# Sensor_Board.net
KiCad netlist of a schematic drawn in Altium Designer
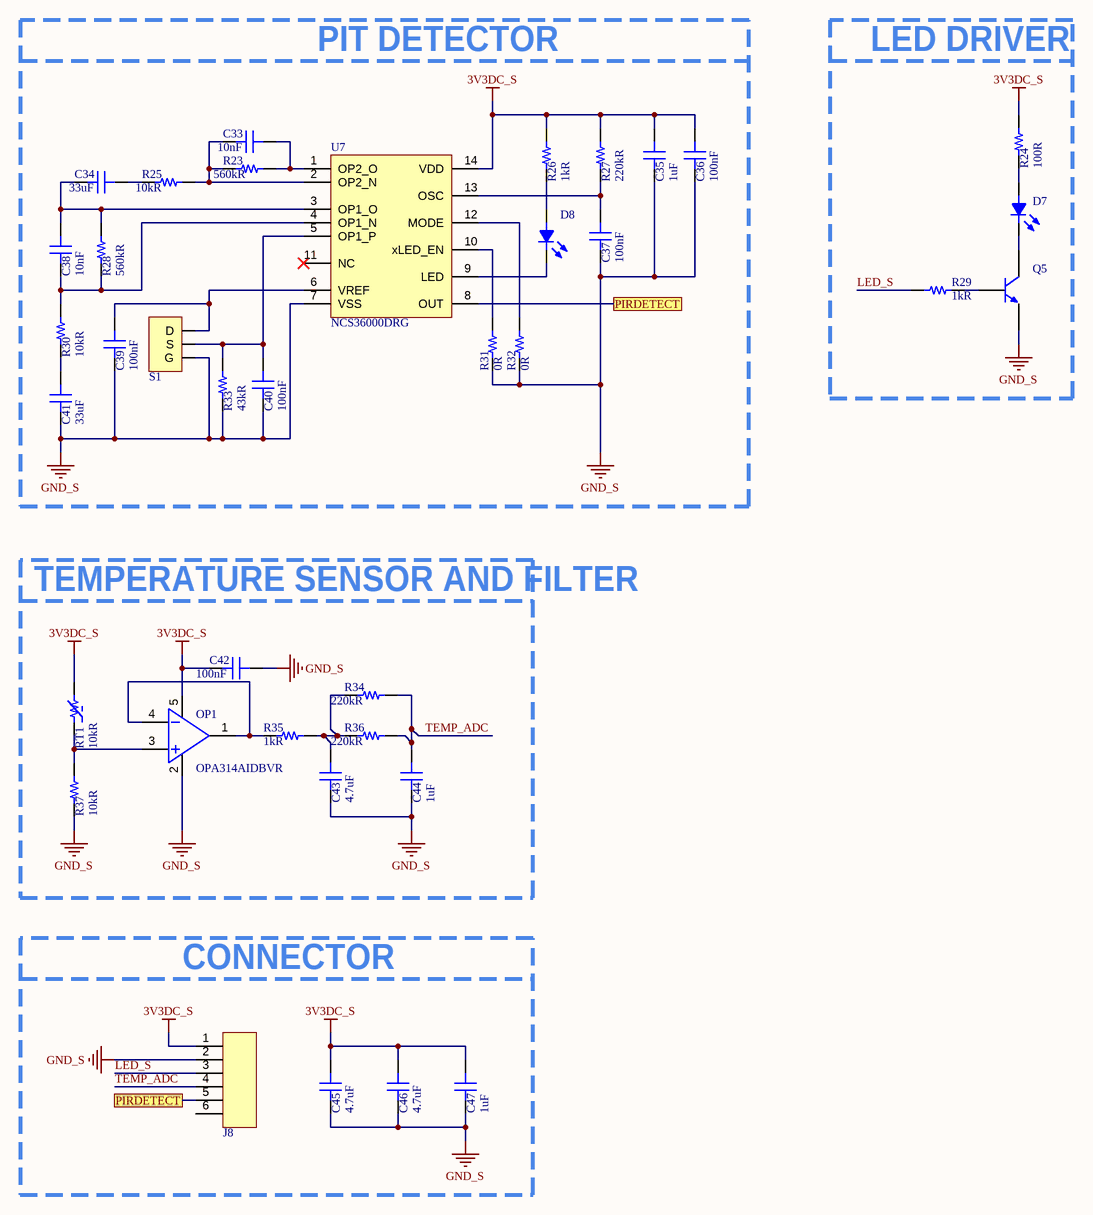
[diagram p0: Sensor_Board.SchDoc]

(export (version "E")
  (design (tool "Eeschema 10.0.6"))
  (components
    (comp (ref "C33")
      (value "0603B103K160CT")
      (footprint "C0603_CER")
      (description "CAP CER 10nF %10 0603 SMD")
      (fields
        (field (name "MANUFACTURER") "Walsin Technologies")
        (field (name "TOLERANCE") "10%")
        (field (name "CAPACITANCE") "10nF")
        (field (name "DESIGNED BY") "Süleyman ARIKAYA")
      )
      (libsource (lib "Arikaya_Lib") (part "CAP CER 10nF 0603"))
    )
    (comp (ref "C34")
      (value "C3216X5R1E336M160AC")
      (footprint "C1206_CER")
      (description "CAP CER 33uF %20 25V 1206 SMD")
      (fields
        (field (name "MANUFACTURER") "TDK")
        (field (name "TOLERANCE") "20%")
        (field (name "CAPACITANCE") "33uF")
        (field (name "DESIGNED BY") "Süleyman ARIKAYA")
      )
      (libsource (lib "Arikaya_Lib") (part "CAP CER 33uF 1206"))
    )
    (comp (ref "C35")
      (value "CL21B105KBFNNNE")
      (footprint "C0805_CER")
      (description "CAP CER 1uF %10 50V X7R 0805 SMD")
      (fields
        (field (name "MANUFACTURER") "Samsung")
        (field (name "TOLERANCE") "10%")
        (field (name "CAPACITANCE") "1uF")
        (field (name "DESIGNED BY") "Süleyman ARIKAYA")
      )
      (libsource (lib "Arikaya_Lib") (part "CAP CER 1uF 0805"))
    )
    (comp (ref "C36")
      (value "C0603C104K5RAC7411")
      (footprint "C0603_CER")
      (description "CAP CER 100nF %10 50V 0603 SMD")
      (fields
        (field (name "MANUFACTURER") "KEMET")
        (field (name "TOLERANCE") "10%")
        (field (name "CAPACITANCE") "100nF")
        (field (name "DESIGNED BY") "Süleyman ARIKAYA")
      )
      (libsource (lib "Arikaya_Lib") (part "CAP CER 100nF 0603"))
    )
    (comp (ref "C37")
      (value "C0603C104K5RAC7411")
      (footprint "C0603_CER")
      (description "CAP CER 100nF %10 50V 0603 SMD")
      (fields
        (field (name "MANUFACTURER") "KEMET")
        (field (name "TOLERANCE") "10%")
        (field (name "CAPACITANCE") "100nF")
        (field (name "DESIGNED BY") "Süleyman ARIKAYA")
      )
      (libsource (lib "Arikaya_Lib") (part "CAP CER 100nF 0603"))
    )
    (comp (ref "C38")
      (value "0603B103K160CT")
      (footprint "C0603_CER")
      (description "CAP CER 10nF %10 0603 SMD")
      (fields
        (field (name "MANUFACTURER") "Walsin Technologies")
        (field (name "TOLERANCE") "10%")
        (field (name "CAPACITANCE") "10nF")
        (field (name "DESIGNED BY") "Süleyman ARIKAYA")
      )
      (libsource (lib "Arikaya_Lib") (part "CAP CER 10nF 0603"))
    )
    (comp (ref "C39")
      (value "C0603C104K5RAC7411")
      (footprint "C0603_CER")
      (description "CAP CER 100nF %10 50V 0603 SMD")
      (fields
        (field (name "MANUFACTURER") "KEMET")
        (field (name "TOLERANCE") "10%")
        (field (name "CAPACITANCE") "100nF")
        (field (name "DESIGNED BY") "Süleyman ARIKAYA")
      )
      (libsource (lib "Arikaya_Lib") (part "CAP CER 100nF 0603"))
    )
    (comp (ref "C40")
      (value "C0603C104K5RAC7411")
      (footprint "C0603_CER")
      (description "CAP CER 100nF %10 50V 0603 SMD")
      (fields
        (field (name "MANUFACTURER") "KEMET")
        (field (name "TOLERANCE") "10%")
        (field (name "CAPACITANCE") "100nF")
        (field (name "DESIGNED BY") "Süleyman ARIKAYA")
      )
      (libsource (lib "Arikaya_Lib") (part "CAP CER 100nF 0603"))
    )
    (comp (ref "C41")
      (value "C3216X5R1E336M160AC")
      (footprint "C1206_CER")
      (description "CAP CER 33uF %20 25V 1206 SMD")
      (fields
        (field (name "MANUFACTURER") "TDK")
        (field (name "TOLERANCE") "20%")
        (field (name "CAPACITANCE") "33uF")
        (field (name "DESIGNED BY") "Süleyman ARIKAYA")
      )
      (libsource (lib "Arikaya_Lib") (part "CAP CER 33uF 1206"))
    )
    (comp (ref "C42")
      (value "C0603C104K5RAC7411")
      (footprint "C0603_CER")
      (description "CAP CER 100nF %10 50V 0603 SMD")
      (fields
        (field (name "MANUFACTURER") "KEMET")
        (field (name "TOLERANCE") "10%")
        (field (name "CAPACITANCE") "100nF")
        (field (name "DESIGNED BY") "Süleyman ARIKAYA")
      )
      (libsource (lib "Arikaya_Lib") (part "CAP CER 100nF 0603"))
    )
    (comp (ref "C43")
      (value "CL21A475KAQNNNE")
      (footprint "C0805_CER")
      (description "CAP CER 4.7uF %10 25V X5R 0805 SMD")
      (fields
        (field (name "MANUFACTURER") "Samsung")
        (field (name "TOLERANCE") "10%")
        (field (name "CAPACITANCE") "4.7uF")
        (field (name "DESIGNED BY") "Süleyman ARIKAYA")
      )
      (libsource (lib "Arikaya_Lib") (part "CAP CER 4.7uF 0805"))
    )
    (comp (ref "C44")
      (value "CL21B105KBFNNNE")
      (footprint "C0805_CER")
      (description "CAP CER 1uF %10 50V X7R 0805 SMD")
      (fields
        (field (name "MANUFACTURER") "Samsung")
        (field (name "TOLERANCE") "10%")
        (field (name "CAPACITANCE") "1uF")
        (field (name "DESIGNED BY") "Süleyman ARIKAYA")
      )
      (libsource (lib "Arikaya_Lib") (part "CAP CER 1uF 0805"))
    )
    (comp (ref "C45")
      (value "CL21A475KAQNNNE")
      (footprint "C0805_CER")
      (description "CAP CER 4.7uF %10 25V X5R 0805 SMD")
      (fields
        (field (name "MANUFACTURER") "Samsung")
        (field (name "TOLERANCE") "10%")
        (field (name "CAPACITANCE") "4.7uF")
        (field (name "DESIGNED BY") "Süleyman ARIKAYA")
      )
      (libsource (lib "Arikaya_Lib") (part "CAP CER 4.7uF 0805"))
    )
    (comp (ref "C46")
      (value "CL21A475KAQNNNE")
      (footprint "C0805_CER")
      (description "CAP CER 4.7uF %10 25V X5R 0805 SMD")
      (fields
        (field (name "MANUFACTURER") "Samsung")
        (field (name "TOLERANCE") "10%")
        (field (name "CAPACITANCE") "4.7uF")
        (field (name "DESIGNED BY") "Süleyman ARIKAYA")
      )
      (libsource (lib "Arikaya_Lib") (part "CAP CER 4.7uF 0805"))
    )
    (comp (ref "C47")
      (value "CL21B105KBFNNNE")
      (footprint "C0805_CER")
      (description "CAP CER 1uF %10 50V X7R 0805 SMD")
      (fields
        (field (name "MANUFACTURER") "Samsung")
        (field (name "TOLERANCE") "10%")
        (field (name "CAPACITANCE") "1uF")
        (field (name "DESIGNED BY") "Süleyman ARIKAYA")
      )
      (libsource (lib "Arikaya_Lib") (part "CAP CER 1uF 0805"))
    )
    (comp (ref "D7")
      (value "LH R974-LP-1-0-20-R18")
      (footprint "LED_RED_0805")
      (description "LED Uni-Color Hyper Red 660nm 2-Pin Chip 0805(2012Metric) T/R")
      (fields
        (field (name "MANUFACTURER") "Osram Opto")
        (field (name "MANUFACTURER PART NUMBER") "LH R974-LP-1")
        (field (name "DESIGNED BY") "Süleyman ARIKAYA")
      )
      (libsource (lib "Arikaya_Lib") (part "LED RED 0805"))
    )
    (comp (ref "D8")
      (value "LTST-C171GKT")
      (footprint "LED_GREEN_0805")
      (description "Green 569nm LED Indication - Discrete 2.1V 0805 (2012 Metric)")
      (fields (field (name "MANUFACTURER") "Vishay Lite-On") (field (name "DESIGNED BY") "Süleyman ARIKAYA"))
      (libsource (lib "Arikaya_Lib") (part "LED GREEN 0805"))
    )
    (comp (ref "J8")
      (value "64800611622")
      (footprint "64800611622_Conn_6Pinn")
      (description "1.50mm 6PIN Connector")
      (fields
        (field (name "MANUFACTURER") "Wurth Electronics")
        (field (name "DESIGNED BY") "Süleyman ARIKAYA")
      )
      (libsource (lib "Arikaya_Lib") (part "64800611622_Conn_6Pin"))
    )
    (comp (ref "OP1")
      (value "OPA314AIDBVR")
      (footprint "SOT23-5")
      (description "General Purpose Amplifier 1 Circuit Rail-to-Rail SOT-23-5")
      (fields
        (field (name "MANUFACTURER") "Texas Instruments")
        (field (name "DESIGNED BY") "Süleyman ARIKAYA")
      )
      (libsource (lib "Arikaya_Lib") (part "OPA314AIDBVR"))
    )
    (comp (ref "Q5")
      (value "MMBT3904-7-F")
      (footprint "SOT-23F")
      (description "NPN Ic=200mA Vceo=40V hfe=100~300 fT=310MHz P=300mW SOT-23")
      (fields (field (name "MANUFACTURER") "Diodes Zetex") (field (name "DESIGNED BY") "Süleyman ARIKAYA"))
      (libsource (lib "Arikaya_Lib") (part "MMBT3904-7-F"))
    )
    (comp (ref "R23")
      (value "RC0603JR-07560KL")
      (footprint "R0603")
      (description "RES 560K OHM 5% 1/10W 0603")
      (fields
        (field (name "MANUFACTURER") "Yageo")
        (field (name "TOLERANCE") "5%")
        (field (name "RESISTANCE") "560kR")
        (field (name "DESIGNED BY") "Süleyman ARIKAYA")
      )
      (libsource (lib "Arikaya_Lib") (part "RES 560K OHM 0603"))
    )
    (comp (ref "R24")
      (value "RC0603JR-07100RL")
      (footprint "R0603")
      (description "RES 100 OHM 5% 1/10W 0603")
      (fields
        (field (name "MANUFACTURER") "Yageo")
        (field (name "TOLERANCE") "5%")
        (field (name "RESISTANCE") "100R")
        (field (name "DESIGNED BY") "Süleyman ARIKAYA")
      )
      (libsource (lib "Arikaya_Lib") (part "RES 100 OHM 0603"))
    )
    (comp (ref "R25")
      (value "RC0603FR-0710KL")
      (footprint "R0603")
      (description "RES SMD 10K OHM 1% 1/10W 0603")
      (fields
        (field (name "MANUFACTURER") "Yageo")
        (field (name "TOLERANCE") "1%")
        (field (name "RESISTANCE") "10kR")
        (field (name "DESIGNED BY") "Süleyman ARIKAYA")
      )
      (libsource (lib "Arikaya_Lib") (part "RES 10K OHM 0603"))
    )
    (comp (ref "R26")
      (value "RC0603FR-071KL")
      (footprint "R0603")
      (description "RES SMD 1K OHM 1% 1/10W 0603")
      (fields
        (field (name "MANUFACTURER") "Yageo")
        (field (name "TOLERANCE") "1%")
        (field (name "RESISTANCE") "1kR")
        (field (name "DESIGNED BY") "Süleyman ARIKAYA")
      )
      (libsource (lib "Arikaya_Lib") (part "RES 1K OHM 0603"))
    )
    (comp (ref "R27")
      (value "RC0603JR-07220KL")
      (footprint "R0603")
      (description "RES 220K OHM 5% 1/10W 0603")
      (fields
        (field (name "MANUFACTURER") "Yageo")
        (field (name "TOLERANCE") "5%")
        (field (name "RESISTANCE") "220kR")
        (field (name "DESIGNED BY") "Süleyman ARIKAYA")
      )
      (libsource (lib "Arikaya_Lib") (part "RES 220K OHM 0603"))
    )
    (comp (ref "R28")
      (value "RC0603JR-07560KL")
      (footprint "R0603")
      (description "RES 560K OHM 5% 1/10W 0603")
      (fields
        (field (name "MANUFACTURER") "Yageo")
        (field (name "TOLERANCE") "5%")
        (field (name "RESISTANCE") "560kR")
        (field (name "DESIGNED BY") "Süleyman ARIKAYA")
      )
      (libsource (lib "Arikaya_Lib") (part "RES 560K OHM 0603"))
    )
    (comp (ref "R29")
      (value "RC0603FR-071KL")
      (footprint "R0603")
      (description "RES SMD 1K OHM 1% 1/10W 0603")
      (fields
        (field (name "MANUFACTURER") "Yageo")
        (field (name "TOLERANCE") "1%")
        (field (name "RESISTANCE") "1kR")
        (field (name "DESIGNED BY") "Süleyman ARIKAYA")
      )
      (libsource (lib "Arikaya_Lib") (part "RES 1K OHM 0603"))
    )
    (comp (ref "R30")
      (value "RC0603FR-0710KL")
      (footprint "R0603")
      (description "RES SMD 10K OHM 1% 1/10W 0603")
      (fields
        (field (name "MANUFACTURER") "Yageo")
        (field (name "TOLERANCE") "1%")
        (field (name "RESISTANCE") "10kR")
        (field (name "DESIGNED BY") "Süleyman ARIKAYA")
      )
      (libsource (lib "Arikaya_Lib") (part "RES 10K OHM 0603"))
    )
    (comp (ref "R31")
      (value "RC0603JR-070RL")
      (footprint "R0603")
      (description "RES SMD 0 OHM JUMPER %1 1/10W 0603")
      (fields
        (field (name "MANUFACTURER") "Yageo")
        (field (name "TOLERANCE") "1%")
        (field (name "RESISTANCE") "0R")
        (field (name "DESIGNED BY") "Süleyman ARIKAYA")
      )
      (libsource (lib "Arikaya_Lib") (part "RES 0 OHM 0603"))
    )
    (comp (ref "R32")
      (value "RC0603JR-070RL")
      (footprint "R0603")
      (description "RES SMD 0 OHM JUMPER %1 1/10W 0603")
      (fields
        (field (name "MANUFACTURER") "Yageo")
        (field (name "TOLERANCE") "1%")
        (field (name "RESISTANCE") "0R")
        (field (name "DESIGNED BY") "Süleyman ARIKAYA")
      )
      (libsource (lib "Arikaya_Lib") (part "RES 0 OHM 0603"))
    )
    (comp (ref "R33")
      (value "RC0603JR-0743KL")
      (footprint "R0603")
      (description "RES 43K OHM 5% 1/10W 0603")
      (fields
        (field (name "MANUFACTURER") "Yageo")
        (field (name "TOLERANCE") "5%")
        (field (name "RESISTANCE") "43kR")
        (field (name "DESIGNED BY") "Süleyman ARIKAYA")
      )
      (libsource (lib "Arikaya_Lib") (part "RES 43K OHM 0603"))
    )
    (comp (ref "R34")
      (value "RC0603JR-07220KL")
      (footprint "R0603")
      (description "RES 220K OHM 5% 1/10W 0603")
      (fields
        (field (name "MANUFACTURER") "Yageo")
        (field (name "TOLERANCE") "5%")
        (field (name "RESISTANCE") "220kR")
        (field (name "DESIGNED BY") "Süleyman ARIKAYA")
      )
      (libsource (lib "Arikaya_Lib") (part "RES 220K OHM 0603"))
    )
    (comp (ref "R35")
      (value "RC0603FR-071KL")
      (footprint "R0603")
      (description "RES SMD 1K OHM 1% 1/10W 0603")
      (fields
        (field (name "MANUFACTURER") "Yageo")
        (field (name "TOLERANCE") "1%")
        (field (name "RESISTANCE") "1kR")
        (field (name "DESIGNED BY") "Süleyman ARIKAYA")
      )
      (libsource (lib "Arikaya_Lib") (part "RES 1K OHM 0603"))
    )
    (comp (ref "R36")
      (value "RC0603JR-07220KL")
      (footprint "R0603")
      (description "RES 220K OHM 5% 1/10W 0603")
      (fields
        (field (name "MANUFACTURER") "Yageo")
        (field (name "TOLERANCE") "5%")
        (field (name "RESISTANCE") "220kR")
        (field (name "DESIGNED BY") "Süleyman ARIKAYA")
      )
      (libsource (lib "Arikaya_Lib") (part "RES 220K OHM 0603"))
    )
    (comp (ref "R37")
      (value "RC0603FR-0710KL")
      (footprint "R0603")
      (description "RES SMD 10K OHM 1% 1/10W 0603")
      (fields
        (field (name "MANUFACTURER") "Yageo")
        (field (name "TOLERANCE") "1%")
        (field (name "RESISTANCE") "10kR")
        (field (name "DESIGNED BY") "Süleyman ARIKAYA")
      )
      (libsource (lib "Arikaya_Lib") (part "RES 10K OHM 0603"))
    )
    (comp (ref "RT1")
      (value "TFPT1206L1002FM")
      (footprint "R1206")
      (description "Thermistor PTC 10K Ohm 1% 1206")
      (fields
        (field (name "MANUFACTURER") "Vishay Dale")
        (field (name "TOLERANCE") "1%")
        (field (name "RESISTANCE") "10kR")
        (field (name "DESIGNED BY") "Süleyman ARIKAYA")
      )
      (libsource (lib "Arikaya_Lib") (part "TFPT1206L1002FM"))
    )
    (comp (ref "S1")
      (value "LHI 878/3902")
      (footprint "LHI 878/3902")
      (description "SENSOR PYRO DETECTOR DUAL MOTION - Sensor PIR (Passive Infrared) TO-205AA, TO-5-3 Metal Can")
      (fields
        (field (name "MANUFACTURER") "Excelitas")
        (field (name "MANUFACTURER PART NUMBER") "LHI878/3902")
        (field (name "DESIGNED BY") "Süleyman ARIKAYA")
      )
      (libsource (lib "Arikaya_Lib") (part "LHI 878/3902"))
    )
    (comp (ref "U7")
      (value "NCS36000DRG")
      (footprint "SOIC14")
      (description "PIR Controller - NCS36000 Series Single 5.75V Passive Infrared Detector Controller (PIR) -SOIC-14")
      (fields
        (field (name "MANUFACTURER") "ON Semiconductor")
        (field (name "DESIGNED BY") "Süleyman ARIKAYA")
      )
      (libsource (lib "Arikaya_Lib") (part "NCS36000DRG"))
    )
  )
  (nets
    (net (code "1") (name "/LED_S") (class "Default")
      (node (ref "J8") (pin "3") (pinfunction "3_3") (pintype "passive"))
      (node (ref "R29") (pin "2") (pinfunction "2_2") (pintype "passive"))
    )
    (net (code "2") (name "/PIRDETECT") (class "Default")
      (node (ref "J8") (pin "5") (pinfunction "5_5") (pintype "passive"))
      (node (ref "U7") (pin "8") (pinfunction "OUT_8") (pintype "passive"))
    )
    (net (code "3") (name "/TEMP_ADC") (class "Default")
      (node (ref "C44") (pin "2") (pinfunction "2_2") (pintype "passive"))
      (node (ref "J8") (pin "4") (pinfunction "4_4") (pintype "passive"))
      (node (ref "R34") (pin "2") (pinfunction "2_2") (pintype "passive"))
      (node (ref "R36") (pin "2") (pinfunction "2_2") (pintype "passive"))
    )
    (net (code "4") (name "3V3DC_S") (class "Default")
      (node (ref "C35") (pin "2") (pinfunction "2_2") (pintype "passive"))
      (node (ref "C36") (pin "2") (pinfunction "2_2") (pintype "passive"))
      (node (ref "C42") (pin "1") (pinfunction "1_1") (pintype "passive"))
      (node (ref "C45") (pin "2") (pinfunction "2_2") (pintype "passive"))
      (node (ref "C46") (pin "2") (pinfunction "2_2") (pintype "passive"))
      (node (ref "C47") (pin "2") (pinfunction "2_2") (pintype "passive"))
      (node (ref "J8") (pin "1") (pinfunction "1_1") (pintype "passive"))
      (node (ref "OP1") (pin "5") (pinfunction "VCC_5") (pintype "passive"))
      (node (ref "R24") (pin "2") (pinfunction "2_2") (pintype "passive"))
      (node (ref "R26") (pin "2") (pinfunction "2_2") (pintype "passive"))
      (node (ref "R27") (pin "2") (pinfunction "2_2") (pintype "passive"))
      (node (ref "RT1") (pin "2") (pinfunction "2_2") (pintype "passive"))
      (node (ref "U7") (pin "14") (pinfunction "VDD_14") (pintype "passive"))
    )
    (net (code "5") (name "GND_S") (class "Default")
      (node (ref "C35") (pin "1") (pinfunction "1_1") (pintype "passive"))
      (node (ref "C36") (pin "1") (pinfunction "1_1") (pintype "passive"))
      (node (ref "C37") (pin "1") (pinfunction "1_1") (pintype "passive"))
      (node (ref "C39") (pin "1") (pinfunction "1_1") (pintype "passive"))
      (node (ref "C40") (pin "1") (pinfunction "1_1") (pintype "passive"))
      (node (ref "C41") (pin "1") (pinfunction "1_1") (pintype "passive"))
      (node (ref "C42") (pin "2") (pinfunction "2_2") (pintype "passive"))
      (node (ref "C43") (pin "1") (pinfunction "1_1") (pintype "passive"))
      (node (ref "C44") (pin "1") (pinfunction "1_1") (pintype "passive"))
      (node (ref "C45") (pin "1") (pinfunction "1_1") (pintype "passive"))
      (node (ref "C46") (pin "1") (pinfunction "1_1") (pintype "passive"))
      (node (ref "C47") (pin "1") (pinfunction "1_1") (pintype "passive"))
      (node (ref "J8") (pin "2") (pinfunction "2_2") (pintype "passive"))
      (node (ref "OP1") (pin "2") (pinfunction "VSS_2") (pintype "passive"))
      (node (ref "Q5") (pin "2") (pinfunction "E_2") (pintype "passive"))
      (node (ref "R31") (pin "1") (pinfunction "1_1") (pintype "passive"))
      (node (ref "R32") (pin "1") (pinfunction "1_1") (pintype "passive"))
      (node (ref "R33") (pin "1") (pinfunction "1_1") (pintype "passive"))
      (node (ref "R37") (pin "1") (pinfunction "1_1") (pintype "passive"))
      (node (ref "S1") (pin "3") (pinfunction "G_3") (pintype "passive"))
      (node (ref "U7") (pin "7") (pinfunction "VSS_7") (pintype "passive"))
    )
    (net (code "6") (name "Net-(C34-Pad2)") (class "Default")
      (node (ref "C34") (pin "2") (pinfunction "2_2") (pintype "passive"))
      (node (ref "R25") (pin "1") (pinfunction "1_1") (pintype "passive"))
    )
    (net (code "7") (name "Net-(C41-Pad2)") (class "Default")
      (node (ref "C41") (pin "2") (pinfunction "2_2") (pintype "passive"))
      (node (ref "R30") (pin "1") (pinfunction "1_1") (pintype "passive"))
    )
    (net (code "8") (name "Net-(C43-Pad2)") (class "Default")
      (node (ref "C43") (pin "2") (pinfunction "2_2") (pintype "passive"))
      (node (ref "R34") (pin "1") (pinfunction "1_1") (pintype "passive"))
      (node (ref "R35") (pin "1") (pinfunction "1_1") (pintype "passive"))
      (node (ref "R36") (pin "1") (pinfunction "1_1") (pintype "passive"))
    )
    (net (code "9") (name "Net-(D7-PadA)") (class "Default")
      (node (ref "D7") (pin "A") (pinfunction "A_A") (pintype "passive"))
      (node (ref "R24") (pin "1") (pinfunction "1_1") (pintype "passive"))
    )
    (net (code "10") (name "Net-(D8-PadA)") (class "Default")
      (node (ref "D8") (pin "A") (pinfunction "A_A") (pintype "passive"))
      (node (ref "R26") (pin "1") (pinfunction "1_1") (pintype "passive"))
    )
    (net (code "11") (name "Net-(OP1-+IN)") (class "Default")
      (node (ref "OP1") (pin "3") (pinfunction "+IN_3") (pintype "passive"))
      (node (ref "R37") (pin "2") (pinfunction "2_2") (pintype "passive"))
      (node (ref "RT1") (pin "1") (pinfunction "1_1") (pintype "passive"))
    )
    (net (code "12") (name "Net-(OP1--IN)") (class "Default")
      (node (ref "OP1") (pin "1") (pinfunction "OUT_1") (pintype "passive"))
      (node (ref "OP1") (pin "4") (pinfunction "-IN_4") (pintype "passive"))
      (node (ref "R35") (pin "2") (pinfunction "2_2") (pintype "passive"))
    )
    (net (code "13") (name "Net-(Q5-B)") (class "Default")
      (node (ref "Q5") (pin "1") (pinfunction "B_1") (pintype "passive"))
      (node (ref "R29") (pin "1") (pinfunction "1_1") (pintype "passive"))
    )
    (net (code "14") (name "Net-(Q5-C)") (class "Default")
      (node (ref "D7") (pin "C") (pinfunction "C_C") (pintype "passive"))
      (node (ref "Q5") (pin "3") (pinfunction "C_3") (pintype "passive"))
    )
    (net (code "15") (name "Net-(S1-D)") (class "Default")
      (node (ref "C39") (pin "2") (pinfunction "2_2") (pintype "passive"))
      (node (ref "S1") (pin "1") (pinfunction "D_1") (pintype "passive"))
      (node (ref "U7") (pin "6") (pinfunction "VREF_6") (pintype "passive"))
    )
    (net (code "16") (name "Net-(S1-S)") (class "Default")
      (node (ref "C40") (pin "2") (pinfunction "2_2") (pintype "passive"))
      (node (ref "R33") (pin "2") (pinfunction "2_2") (pintype "passive"))
      (node (ref "S1") (pin "2") (pinfunction "S_2") (pintype "passive"))
      (node (ref "U7") (pin "5") (pinfunction "OP1_P_5") (pintype "passive"))
    )
    (net (code "17") (name "Net-(U7-LED)") (class "Default")
      (node (ref "D8") (pin "C") (pinfunction "C_C") (pintype "passive"))
      (node (ref "U7") (pin "9") (pinfunction "LED_9") (pintype "passive"))
    )
    (net (code "18") (name "Net-(U7-MODE)") (class "Default")
      (node (ref "R32") (pin "2") (pinfunction "2_2") (pintype "passive"))
      (node (ref "U7") (pin "12") (pinfunction "MODE_12") (pintype "passive"))
    )
    (net (code "19") (name "Net-(U7-OP1_N)") (class "Default")
      (node (ref "C38") (pin "1") (pinfunction "1_1") (pintype "passive"))
      (node (ref "R28") (pin "1") (pinfunction "1_1") (pintype "passive"))
      (node (ref "R30") (pin "2") (pinfunction "2_2") (pintype "passive"))
      (node (ref "U7") (pin "4") (pinfunction "OP1_N_4") (pintype "passive"))
    )
    (net (code "20") (name "Net-(U7-OP1_O)") (class "Default")
      (node (ref "C34") (pin "1") (pinfunction "1_1") (pintype "passive"))
      (node (ref "C38") (pin "2") (pinfunction "2_2") (pintype "passive"))
      (node (ref "R28") (pin "2") (pinfunction "2_2") (pintype "passive"))
      (node (ref "U7") (pin "3") (pinfunction "OP1_O_3") (pintype "passive"))
    )
    (net (code "21") (name "Net-(U7-OP2_N)") (class "Default")
      (node (ref "C33") (pin "1") (pinfunction "1_1") (pintype "passive"))
      (node (ref "R23") (pin "1") (pinfunction "1_1") (pintype "passive"))
      (node (ref "R25") (pin "2") (pinfunction "2_2") (pintype "passive"))
      (node (ref "U7") (pin "2") (pinfunction "OP2_N_2") (pintype "passive"))
    )
    (net (code "22") (name "Net-(U7-OP2_O)") (class "Default")
      (node (ref "C33") (pin "2") (pinfunction "2_2") (pintype "passive"))
      (node (ref "R23") (pin "2") (pinfunction "2_2") (pintype "passive"))
      (node (ref "U7") (pin "1") (pinfunction "OP2_O_1") (pintype "passive"))
    )
    (net (code "23") (name "Net-(U7-OSC)") (class "Default")
      (node (ref "C37") (pin "2") (pinfunction "2_2") (pintype "passive"))
      (node (ref "R27") (pin "1") (pinfunction "1_1") (pintype "passive"))
      (node (ref "U7") (pin "13") (pinfunction "OSC_13") (pintype "passive"))
    )
    (net (code "24") (name "Net-(U7-xLED_EN)") (class "Default")
      (node (ref "R31") (pin "2") (pinfunction "2_2") (pintype "passive"))
      (node (ref "U7") (pin "10") (pinfunction "xLED_EN_10") (pintype "passive"))
    )
    (net (code "25") (name "unconnected-(J8-Pad6)") (class "Default")
      (node (ref "J8") (pin "6") (pinfunction "6_6") (pintype "passive"))
    )
    (net (code "26") (name "unconnected-(U7-NC-Pad11)") (class "Default")
      (node (ref "U7") (pin "11") (pinfunction "NC_11") (pintype "passive+no_connect"))
    )
  )
)
